# IO_Expanders.net
KiCad netlist of a schematic drawn in Altium Designer
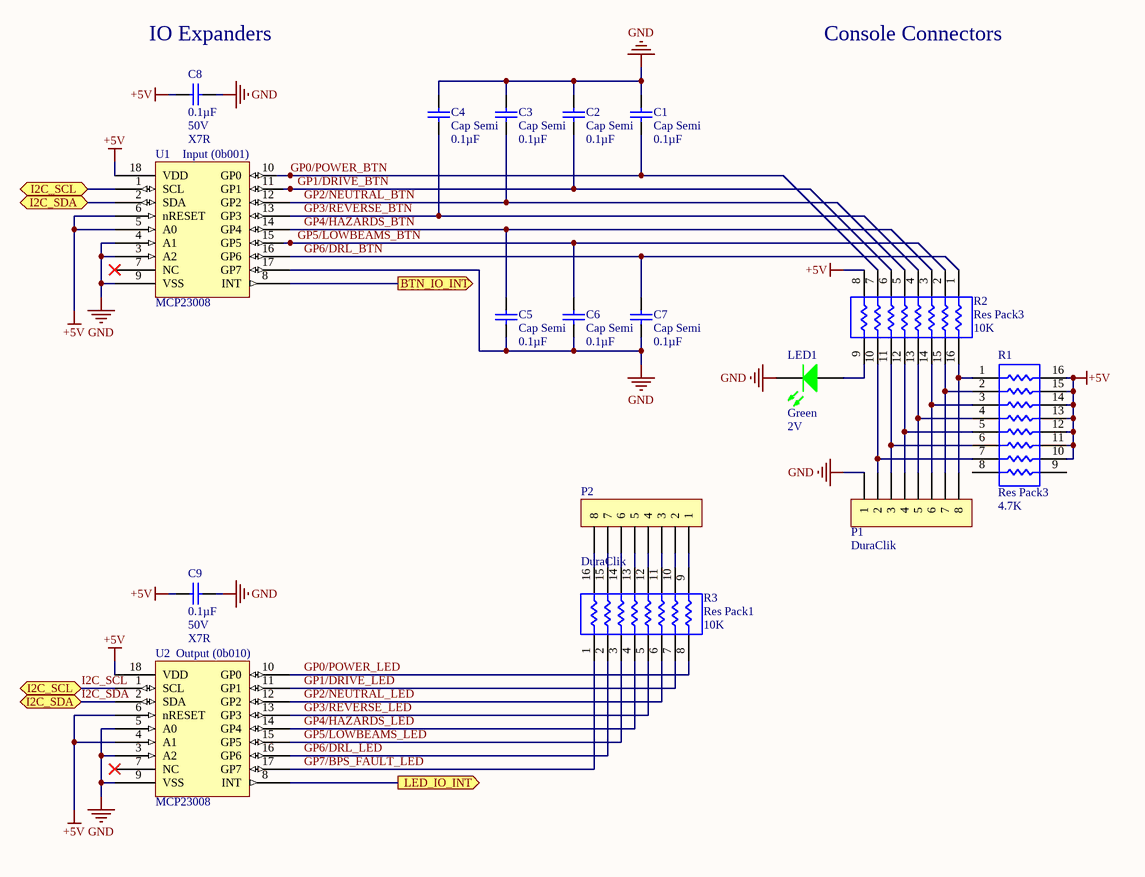
[diagram p0: IO_Expanders.SchDoc]

(export (version "E")
  (design (tool "Eeschema 10.0.6"))
  (components
    (comp (ref "C1")
      (value "Cap Semi")
      (footprint "C1206")
      (description "Capacitor (Semiconductor SIM Model)")
      (fields (field (name "ALTIUM_VALUE") "0.1µF") (field (name "PUBLISHER") "Altium Limited"))
      (libsource (lib "Miscellaneous Devices") (part "Cap Semi"))
    )
    (comp (ref "C2")
      (value "Cap Semi")
      (footprint "C1206")
      (description "Capacitor (Semiconductor SIM Model)")
      (fields (field (name "ALTIUM_VALUE") "0.1µF") (field (name "PUBLISHER") "Altium Limited"))
      (libsource (lib "Miscellaneous Devices") (part "Cap Semi"))
    )
    (comp (ref "C3")
      (value "Cap Semi")
      (footprint "C1206")
      (description "Capacitor (Semiconductor SIM Model)")
      (fields (field (name "ALTIUM_VALUE") "0.1µF") (field (name "PUBLISHER") "Altium Limited"))
      (libsource (lib "Miscellaneous Devices") (part "Cap Semi"))
    )
    (comp (ref "C4")
      (value "Cap Semi")
      (footprint "C1206")
      (description "Capacitor (Semiconductor SIM Model)")
      (fields (field (name "ALTIUM_VALUE") "0.1µF") (field (name "PUBLISHER") "Altium Limited"))
      (libsource (lib "Miscellaneous Devices") (part "Cap Semi"))
    )
    (comp (ref "C5")
      (value "Cap Semi")
      (footprint "C1206")
      (description "Capacitor (Semiconductor SIM Model)")
      (fields (field (name "ALTIUM_VALUE") "0.1µF") (field (name "PUBLISHER") "Altium Limited"))
      (libsource (lib "Miscellaneous Devices") (part "Cap Semi"))
    )
    (comp (ref "C6")
      (value "Cap Semi")
      (footprint "C1206")
      (description "Capacitor (Semiconductor SIM Model)")
      (fields (field (name "ALTIUM_VALUE") "0.1µF") (field (name "PUBLISHER") "Altium Limited"))
      (libsource (lib "Miscellaneous Devices") (part "Cap Semi"))
    )
    (comp (ref "C7")
      (value "Cap Semi")
      (footprint "C1206")
      (description "Capacitor (Semiconductor SIM Model)")
      (fields (field (name "ALTIUM_VALUE") "0.1µF") (field (name "PUBLISHER") "Altium Limited"))
      (libsource (lib "Miscellaneous Devices") (part "Cap Semi"))
    )
    (comp (ref "C8")
      (value "CAP CER 0.1UF 50V 10% X7R 0603")
      (footprint "CAP, 0603")
      (description "0.10µF ±10% 50V Ceramic Capacitor X7R 0603 (1608 Metric)")
      (fields
        (field (name "TOLERANCE") "±10%")
        (field (name "CAPACITANCE") "0.1µF")
        (field (name "VOLTAGE") "50V")
        (field (name "TEMPERATURE COEFFICIENT") "X7R")
      )
      (libsource (lib "Schematic Diagrams") (part "CAP CER 0.1UF 50V 10% X7R 0603"))
    )
    (comp (ref "C9")
      (value "CAP CER 0.1UF 50V 10% X7R 0603")
      (footprint "CAP, 0603")
      (description "0.10µF ±10% 50V Ceramic Capacitor X7R 0603 (1608 Metric)")
      (fields
        (field (name "TOLERANCE") "±10%")
        (field (name "CAPACITANCE") "0.1µF")
        (field (name "VOLTAGE") "50V")
        (field (name "TEMPERATURE COEFFICIENT") "X7R")
      )
      (libsource (lib "Schematic Diagrams") (part "CAP CER 0.1UF 50V 10% X7R 0603"))
    )
    (comp (ref "LED1")
      (value "LED GREEN CLEAR 2V 0603")
      (footprint "LED_0603")
      (description "Green 572nm LED Indication - Discrete 2V 0603 (1608 Metric)")
      (fields
        (field (name "MANUFACTURER") "Wurth Electronics Inc.")
        (field (name "MANUFACTURER PART NUMBER") "150060VS75000")
        (field (name "COLOR") "Green")
        (field (name "VOLTAGE - FORWARD (VF) (TYP)") "2V")
      )
      (libsource (lib "Schematic Diagrams") (part "LED GREEN CLEAR 2V 0603"))
    )
    (comp (ref "P1")
      (value "CONN 8POS DURA-CLIK 0.079\"")
      (footprint "CONN, 8POS Dura-Clik")
      (description "8 Positions Header Connector 0.079\" (2.00mm) Surface Mount Tin")
      (fields (field (name "SERIES") "DuraClik"))
      (libsource (lib "") (part "CONN 8POS DURA-CLIK 0.079{dblquote}_1"))
    )
    (comp (ref "P2")
      (value "CONN 8POS DURA-CLIK 0.079\"")
      (footprint "CONN, 8POS Dura-Clik")
      (description "8 Positions Header Connector 0.079\" (2.00mm) Surface Mount Tin")
      (fields (field (name "SERIES") "DuraClik"))
      (libsource (lib "Schematic Diagrams") (part "CONN 8POS DURA-CLIK 0.079{dblquote}"))
    )
    (comp (ref "R1")
      (value "Res Pack3")
      (footprint "SO-16_N")
      (description "Isolated Resistor Network")
      (fields (field (name "ALTIUM_VALUE") "4.7K") (field (name "PUBLISHER") "Altium Limited"))
      (libsource (lib "Miscellaneous Devices") (part "Res Pack3"))
    )
    (comp (ref "R2")
      (value "Res Pack3")
      (footprint "SO-16_N")
      (description "Isolated Resistor Network")
      (fields (field (name "ALTIUM_VALUE") "10K") (field (name "PUBLISHER") "Altium Limited"))
      (libsource (lib "Miscellaneous Devices") (part "Res Pack3"))
    )
    (comp (ref "R3")
      (value "Res Pack1")
      (footprint "SO-16_N")
      (description "Isolated Resistor Network")
      (fields (field (name "ALTIUM_VALUE") "10K") (field (name "PUBLISHER") "Altium Limited"))
      (libsource (lib "Miscellaneous Devices") (part "Res Pack3"))
    )
    (comp (ref "U1")
      (value "MCP23008")
      (footprint "IC 18SOIC")
      (description "MCP23008 I/O Expander 8B+1Int 18P SOIC")
      (fields
        (field (name "MANUFACTURER") "Microchip Technology")
        (field (name "MANUFACTURER PART NUMBER") "MCP23008T-E/SO")
      )
      (libsource (lib "Schematic Diagrams") (part "IC I/O EXPANDER I2C 8B 18SOIC"))
    )
    (comp (ref "U2")
      (value "MCP23008")
      (footprint "IC 18SOIC")
      (description "MCP23008 I/O Expander 8B+1Int 18P SOIC")
      (fields
        (field (name "MANUFACTURER") "Microchip Technology")
        (field (name "MANUFACTURER PART NUMBER") "MCP23008T-E/SO")
      )
      (libsource (lib "Schematic Diagrams") (part "IC I/O EXPANDER I2C 8B 18SOIC"))
    )
  )
  (nets
    (net (code "1") (name "+5V") (class "Default")
      (node (ref "C8") (pin "1") (pinfunction "1_1") (pintype "passive"))
      (node (ref "C9") (pin "1") (pinfunction "1_1") (pintype "passive"))
      (node (ref "R1") (pin "10") (pinfunction "10_10") (pintype "passive"))
      (node (ref "R1") (pin "11") (pinfunction "11_11") (pintype "passive"))
      (node (ref "R1") (pin "12") (pinfunction "12_12") (pintype "passive"))
      (node (ref "R1") (pin "13") (pinfunction "13_13") (pintype "passive"))
      (node (ref "R1") (pin "14") (pinfunction "14_14") (pintype "passive"))
      (node (ref "R1") (pin "15") (pinfunction "15_15") (pintype "passive"))
      (node (ref "R1") (pin "16") (pinfunction "16_16") (pintype "passive"))
      (node (ref "R2") (pin "8") (pinfunction "8_8") (pintype "passive"))
      (node (ref "U1") (pin "18") (pinfunction "VDD_18") (pintype "power_in"))
      (node (ref "U1") (pin "5") (pinfunction "A0_5") (pintype "input"))
      (node (ref "U1") (pin "6") (pinfunction "nRESET_6") (pintype "input"))
      (node (ref "U2") (pin "18") (pinfunction "VDD_18") (pintype "power_in"))
      (node (ref "U2") (pin "4") (pinfunction "A1_4") (pintype "input"))
      (node (ref "U2") (pin "6") (pinfunction "nRESET_6") (pintype "input"))
    )
    (net (code "2") (name "/BTN_IO_INT") (class "Default")
      (node (ref "U1") (pin "8") (pinfunction "INT_8") (pintype "output"))
    )
    (net (code "3") (name "/GP0{slash}POWER_BTN") (class "Default")
      (node (ref "C1") (pin "1") (pinfunction "1_1") (pintype "passive"))
      (node (ref "R2") (pin "7") (pinfunction "7_7") (pintype "passive"))
      (node (ref "U1") (pin "10") (pinfunction "GP0_10") (pintype "bidirectional"))
    )
    (net (code "4") (name "/GP0{slash}POWER_LED") (class "Default")
      (node (ref "R3") (pin "8") (pinfunction "8_8") (pintype "passive"))
      (node (ref "U2") (pin "10") (pinfunction "GP0_10") (pintype "bidirectional"))
    )
    (net (code "5") (name "/GP1{slash}DRIVE_BTN") (class "Default")
      (node (ref "C2") (pin "2") (pinfunction "2_2") (pintype "passive"))
      (node (ref "R2") (pin "6") (pinfunction "6_6") (pintype "passive"))
      (node (ref "U1") (pin "11") (pinfunction "GP1_11") (pintype "bidirectional"))
    )
    (net (code "6") (name "/GP1{slash}DRIVE_LED") (class "Default")
      (node (ref "R3") (pin "7") (pinfunction "7_7") (pintype "passive"))
      (node (ref "U2") (pin "11") (pinfunction "GP1_11") (pintype "bidirectional"))
    )
    (net (code "7") (name "/GP2{slash}NEUTRAL_BTN") (class "Default")
      (node (ref "C3") (pin "2") (pinfunction "2_2") (pintype "passive"))
      (node (ref "R2") (pin "5") (pinfunction "5_5") (pintype "passive"))
      (node (ref "U1") (pin "12") (pinfunction "GP2_12") (pintype "bidirectional"))
    )
    (net (code "8") (name "/GP2{slash}NEUTRAL_LED") (class "Default")
      (node (ref "R3") (pin "6") (pinfunction "6_6") (pintype "passive"))
      (node (ref "U2") (pin "12") (pinfunction "GP2_12") (pintype "bidirectional"))
    )
    (net (code "9") (name "/GP3{slash}REVERSE_BTN") (class "Default")
      (node (ref "C4") (pin "2") (pinfunction "2_2") (pintype "passive"))
      (node (ref "R2") (pin "4") (pinfunction "4_4") (pintype "passive"))
      (node (ref "U1") (pin "13") (pinfunction "GP3_13") (pintype "bidirectional"))
    )
    (net (code "10") (name "/GP3{slash}REVERSE_LED") (class "Default")
      (node (ref "R3") (pin "5") (pinfunction "5_5") (pintype "passive"))
      (node (ref "U2") (pin "13") (pinfunction "GP3_13") (pintype "bidirectional"))
    )
    (net (code "11") (name "/GP4{slash}HAZARDS_BTN") (class "Default")
      (node (ref "C5") (pin "1") (pinfunction "1_1") (pintype "passive"))
      (node (ref "R2") (pin "3") (pinfunction "3_3") (pintype "passive"))
      (node (ref "U1") (pin "14") (pinfunction "GP4_14") (pintype "bidirectional"))
    )
    (net (code "12") (name "/GP4{slash}HAZARDS_LED") (class "Default")
      (node (ref "R3") (pin "4") (pinfunction "4_4") (pintype "passive"))
      (node (ref "U2") (pin "14") (pinfunction "GP4_14") (pintype "bidirectional"))
    )
    (net (code "13") (name "/GP5{slash}LOWBEAMS_BTN") (class "Default")
      (node (ref "C6") (pin "1") (pinfunction "1_1") (pintype "passive"))
      (node (ref "R2") (pin "2") (pinfunction "2_2") (pintype "passive"))
      (node (ref "U1") (pin "15") (pinfunction "GP5_15") (pintype "bidirectional"))
    )
    (net (code "14") (name "/GP5{slash}LOWBEAMS_LED") (class "Default")
      (node (ref "R3") (pin "3") (pinfunction "3_3") (pintype "passive"))
      (node (ref "U2") (pin "15") (pinfunction "GP5_15") (pintype "bidirectional"))
    )
    (net (code "15") (name "/GP6{slash}DRL_BTN") (class "Default")
      (node (ref "C7") (pin "1") (pinfunction "1_1") (pintype "passive"))
      (node (ref "R2") (pin "1") (pinfunction "1_1") (pintype "passive"))
      (node (ref "U1") (pin "16") (pinfunction "GP6_16") (pintype "bidirectional"))
    )
    (net (code "16") (name "/GP6{slash}DRL_LED") (class "Default")
      (node (ref "R3") (pin "2") (pinfunction "2_2") (pintype "passive"))
      (node (ref "U2") (pin "16") (pinfunction "GP6_16") (pintype "bidirectional"))
    )
    (net (code "17") (name "/GP7{slash}BPS_FAULT_LED") (class "Default")
      (node (ref "R3") (pin "1") (pinfunction "1_1") (pintype "passive"))
      (node (ref "U2") (pin "17") (pinfunction "GP7_17") (pintype "bidirectional"))
    )
    (net (code "18") (name "/I2C_SCL") (class "Default")
      (node (ref "U1") (pin "1") (pinfunction "SCL_1") (pintype "bidirectional"))
      (node (ref "U2") (pin "1") (pinfunction "SCL_1") (pintype "bidirectional"))
    )
    (net (code "19") (name "/I2C_SDA") (class "Default")
      (node (ref "U1") (pin "2") (pinfunction "SDA_2") (pintype "bidirectional"))
      (node (ref "U2") (pin "2") (pinfunction "SDA_2") (pintype "bidirectional"))
    )
    (net (code "20") (name "/LED_IO_INT") (class "Default")
      (node (ref "U2") (pin "8") (pinfunction "INT_8") (pintype "output"))
    )
    (net (code "21") (name "GND") (class "Default")
      (node (ref "C1") (pin "2") (pinfunction "2_2") (pintype "passive"))
      (node (ref "C2") (pin "1") (pinfunction "1_1") (pintype "passive"))
      (node (ref "C3") (pin "1") (pinfunction "1_1") (pintype "passive"))
      (node (ref "C4") (pin "1") (pinfunction "1_1") (pintype "passive"))
      (node (ref "C5") (pin "2") (pinfunction "2_2") (pintype "passive"))
      (node (ref "C6") (pin "2") (pinfunction "2_2") (pintype "passive"))
      (node (ref "C7") (pin "2") (pinfunction "2_2") (pintype "passive"))
      (node (ref "C8") (pin "2") (pinfunction "2_2") (pintype "passive"))
      (node (ref "C9") (pin "2") (pinfunction "2_2") (pintype "passive"))
      (node (ref "LED1") (pin "2") (pinfunction "K_2") (pintype "passive"))
      (node (ref "P1") (pin "1") (pinfunction "1_1") (pintype "passive"))
      (node (ref "U1") (pin "17") (pinfunction "GP7_17") (pintype "bidirectional"))
      (node (ref "U1") (pin "3") (pinfunction "A2_3") (pintype "input"))
      (node (ref "U1") (pin "4") (pinfunction "A1_4") (pintype "input"))
      (node (ref "U1") (pin "9") (pinfunction "VSS_9") (pintype "power_in"))
      (node (ref "U2") (pin "3") (pinfunction "A2_3") (pintype "input"))
      (node (ref "U2") (pin "5") (pinfunction "A0_5") (pintype "input"))
      (node (ref "U2") (pin "9") (pinfunction "VSS_9") (pintype "power_in"))
    )
    (net (code "22") (name "Net-(LED1-A)") (class "Default")
      (node (ref "LED1") (pin "1") (pinfunction "A_1") (pintype "passive"))
      (node (ref "R2") (pin "9") (pinfunction "9_9") (pintype "passive"))
    )
    (net (code "23") (name "Net-(P1-Pad2)") (class "Default")
      (node (ref "P1") (pin "2") (pinfunction "2_2") (pintype "passive"))
      (node (ref "R1") (pin "7") (pinfunction "7_7") (pintype "passive"))
      (node (ref "R2") (pin "10") (pinfunction "10_10") (pintype "passive"))
    )
    (net (code "24") (name "Net-(P1-Pad3)") (class "Default")
      (node (ref "P1") (pin "3") (pinfunction "3_3") (pintype "passive"))
      (node (ref "R1") (pin "6") (pinfunction "6_6") (pintype "passive"))
      (node (ref "R2") (pin "11") (pinfunction "11_11") (pintype "passive"))
    )
    (net (code "25") (name "Net-(P1-Pad4)") (class "Default")
      (node (ref "P1") (pin "4") (pinfunction "4_4") (pintype "passive"))
      (node (ref "R1") (pin "5") (pinfunction "5_5") (pintype "passive"))
      (node (ref "R2") (pin "12") (pinfunction "12_12") (pintype "passive"))
    )
    (net (code "26") (name "Net-(P1-Pad5)") (class "Default")
      (node (ref "P1") (pin "5") (pinfunction "5_5") (pintype "passive"))
      (node (ref "R1") (pin "4") (pinfunction "4_4") (pintype "passive"))
      (node (ref "R2") (pin "13") (pinfunction "13_13") (pintype "passive"))
    )
    (net (code "27") (name "Net-(P1-Pad6)") (class "Default")
      (node (ref "P1") (pin "6") (pinfunction "6_6") (pintype "passive"))
      (node (ref "R1") (pin "3") (pinfunction "3_3") (pintype "passive"))
      (node (ref "R2") (pin "14") (pinfunction "14_14") (pintype "passive"))
    )
    (net (code "28") (name "Net-(P1-Pad7)") (class "Default")
      (node (ref "P1") (pin "7") (pinfunction "7_7") (pintype "passive"))
      (node (ref "R1") (pin "2") (pinfunction "2_2") (pintype "passive"))
      (node (ref "R2") (pin "15") (pinfunction "15_15") (pintype "passive"))
    )
    (net (code "29") (name "Net-(P1-Pad8)") (class "Default")
      (node (ref "P1") (pin "8") (pinfunction "8_8") (pintype "passive"))
      (node (ref "R1") (pin "1") (pinfunction "1_1") (pintype "passive"))
      (node (ref "R2") (pin "16") (pinfunction "16_16") (pintype "passive"))
    )
    (net (code "30") (name "Net-(P2-Pad1)") (class "Default")
      (node (ref "P2") (pin "1") (pinfunction "1_1") (pintype "passive"))
      (node (ref "R3") (pin "9") (pinfunction "9_9") (pintype "passive"))
    )
    (net (code "31") (name "Net-(P2-Pad2)") (class "Default")
      (node (ref "P2") (pin "2") (pinfunction "2_2") (pintype "passive"))
      (node (ref "R3") (pin "10") (pinfunction "10_10") (pintype "passive"))
    )
    (net (code "32") (name "Net-(P2-Pad3)") (class "Default")
      (node (ref "P2") (pin "3") (pinfunction "3_3") (pintype "passive"))
      (node (ref "R3") (pin "11") (pinfunction "11_11") (pintype "passive"))
    )
    (net (code "33") (name "Net-(P2-Pad4)") (class "Default")
      (node (ref "P2") (pin "4") (pinfunction "4_4") (pintype "passive"))
      (node (ref "R3") (pin "12") (pinfunction "12_12") (pintype "passive"))
    )
    (net (code "34") (name "Net-(P2-Pad5)") (class "Default")
      (node (ref "P2") (pin "5") (pinfunction "5_5") (pintype "passive"))
      (node (ref "R3") (pin "13") (pinfunction "13_13") (pintype "passive"))
    )
    (net (code "35") (name "Net-(P2-Pad6)") (class "Default")
      (node (ref "P2") (pin "6") (pinfunction "6_6") (pintype "passive"))
      (node (ref "R3") (pin "14") (pinfunction "14_14") (pintype "passive"))
    )
    (net (code "36") (name "Net-(P2-Pad7)") (class "Default")
      (node (ref "P2") (pin "7") (pinfunction "7_7") (pintype "passive"))
      (node (ref "R3") (pin "15") (pinfunction "15_15") (pintype "passive"))
    )
    (net (code "37") (name "Net-(P2-Pad8)") (class "Default")
      (node (ref "P2") (pin "8") (pinfunction "8_8") (pintype "passive"))
      (node (ref "R3") (pin "16") (pinfunction "16_16") (pintype "passive"))
    )
    (net (code "38") (name "unconnected-(R1-Pad8)") (class "Default")
      (node (ref "R1") (pin "8") (pinfunction "8_8") (pintype "passive"))
    )
    (net (code "39") (name "unconnected-(R1-Pad9)") (class "Default")
      (node (ref "R1") (pin "9") (pinfunction "9_9") (pintype "passive"))
    )
    (net (code "40") (name "unconnected-(U1-NC-Pad7)") (class "Default")
      (node (ref "U1") (pin "7") (pinfunction "NC_7") (pintype "passive+no_connect"))
    )
    (net (code "41") (name "unconnected-(U2-NC-Pad7)") (class "Default")
      (node (ref "U2") (pin "7") (pinfunction "NC_7") (pintype "passive+no_connect"))
    )
  )
)
